# MT3608-dip-board.net
KiCad netlist of a schematic drawn in EAGLE
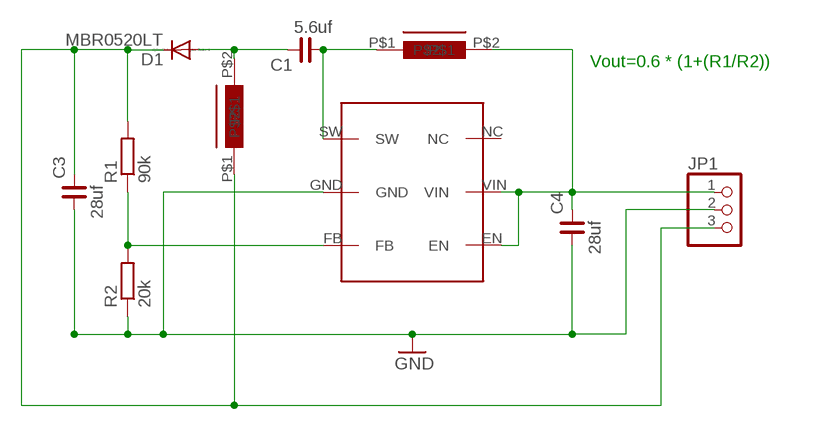
[diagram p0: schematic, sheet 1]

(export (version "E")
  (design (tool "Eeschema 10.0.6"))
  (components
    (comp (ref "22UH")
      (value "CDRH74NP-220MC-B")
      (footprint "eagle-import:CDRH74NP-220MC-B")
      (libsource (lib "eagle-import") (part "CDRH74NP-220MC-B"))
    )
    (comp (ref "C1")
      (value "5.6uf")
      (footprint "eagle-import:C0805")
      (libsource (lib "eagle-import") (part "C_0805"))
    )
    (comp (ref "C3")
      (value "28uf")
      (footprint "eagle-import:C0805")
      (libsource (lib "eagle-import") (part "C_0805"))
    )
    (comp (ref "C4")
      (value "28uf")
      (footprint "eagle-import:C0805")
      (libsource (lib "eagle-import") (part "C_0805"))
    )
    (comp (ref "D1")
      (value "MBR0520LT")
      (footprint "eagle-import:SOD123")
      (libsource (lib "eagle-import") (part "MBR0520LT"))
    )
    (comp (ref "JP1")
      (value "PINHD-1X3")
      (footprint "eagle-import:1X03")
      (libsource (lib "eagle-import") (part "PINHD-1X3"))
    )
    (comp (ref "R1")
      (value "90k")
      (footprint "eagle-import:R0805")
      (libsource (lib "eagle-import") (part "R-EU_R0805"))
    )
    (comp (ref "R2")
      (value "20k")
      (footprint "eagle-import:R0805")
      (libsource (lib "eagle-import") (part "R-EU_R0805"))
    )
    (comp (ref "U$1")
      (value "MT3608")
      (footprint "eagle-import:MT3608")
      (libsource (lib "eagle-import") (part "MT3608"))
    )
    (comp (ref "U$3")
      (value "CDRH74NP-220MC-B")
      (footprint "eagle-import:CDRH74NP-220MC-B")
      (libsource (lib "eagle-import") (part "CDRH74NP-220MC-B"))
    )
  )
  (nets
    (net (code "1") (name "GND") (class "Default")
      (node (ref "C3") (pin "1") (pinfunction "1_1") (pintype "passive"))
      (node (ref "C4") (pin "1") (pinfunction "1_1") (pintype "passive"))
      (node (ref "JP1") (pin "2") (pinfunction "2_2") (pintype "passive"))
      (node (ref "R2") (pin "1") (pinfunction "1_1") (pintype "passive"))
      (node (ref "U$1") (pin "GND") (pinfunction "GND_GND") (pintype "bidirectional"))
    )
    (net (code "2") (name "Net-(22UH-PadP$1)") (class "Default")
      (node (ref "22UH") (pin "P$1") (pinfunction "P$1_P$1") (pintype "bidirectional"))
      (node (ref "C3") (pin "2") (pinfunction "2_2") (pintype "passive"))
      (node (ref "D1") (pin "C") (pinfunction "C_C") (pintype "passive"))
      (node (ref "JP1") (pin "3") (pinfunction "3_3") (pintype "passive"))
      (node (ref "R1") (pin "2") (pinfunction "2_2") (pintype "passive"))
    )
    (net (code "3") (name "Net-(22UH-PadP$2)") (class "Default")
      (node (ref "22UH") (pin "P$2") (pinfunction "P$2_P$2") (pintype "bidirectional"))
      (node (ref "C1") (pin "2") (pinfunction "2_2") (pintype "passive"))
      (node (ref "D1") (pin "A") (pinfunction "A_A") (pintype "passive"))
    )
    (net (code "4") (name "Net-(C1-Pad1)") (class "Default")
      (node (ref "C1") (pin "1") (pinfunction "1_1") (pintype "passive"))
      (node (ref "U$1") (pin "SW") (pinfunction "SW_SW") (pintype "bidirectional"))
      (node (ref "U$3") (pin "P$1") (pinfunction "P$1_P$1") (pintype "bidirectional"))
    )
    (net (code "5") (name "Net-(C4-Pad2)") (class "Default")
      (node (ref "C4") (pin "2") (pinfunction "2_2") (pintype "passive"))
      (node (ref "JP1") (pin "1") (pinfunction "1_1") (pintype "passive"))
      (node (ref "U$1") (pin "EN") (pinfunction "EN_EN") (pintype "bidirectional"))
      (node (ref "U$1") (pin "VIN") (pinfunction "VIN_VIN") (pintype "bidirectional"))
      (node (ref "U$3") (pin "P$2") (pinfunction "P$2_P$2") (pintype "bidirectional"))
    )
    (net (code "6") (name "Net-(R1-Pad1)") (class "Default")
      (node (ref "R1") (pin "1") (pinfunction "1_1") (pintype "passive"))
      (node (ref "R2") (pin "2") (pinfunction "2_2") (pintype "passive"))
      (node (ref "U$1") (pin "FB") (pinfunction "FB_FB") (pintype "bidirectional"))
    )
    (net (code "7") (name "unconnected-(U$1-PadNC)") (class "Default")
      (node (ref "U$1") (pin "NC") (pinfunction "NC_NC") (pintype "bidirectional"))
    )
  )
)
